# Charge_Controller.net
KiCad netlist of a schematic drawn in EAGLE
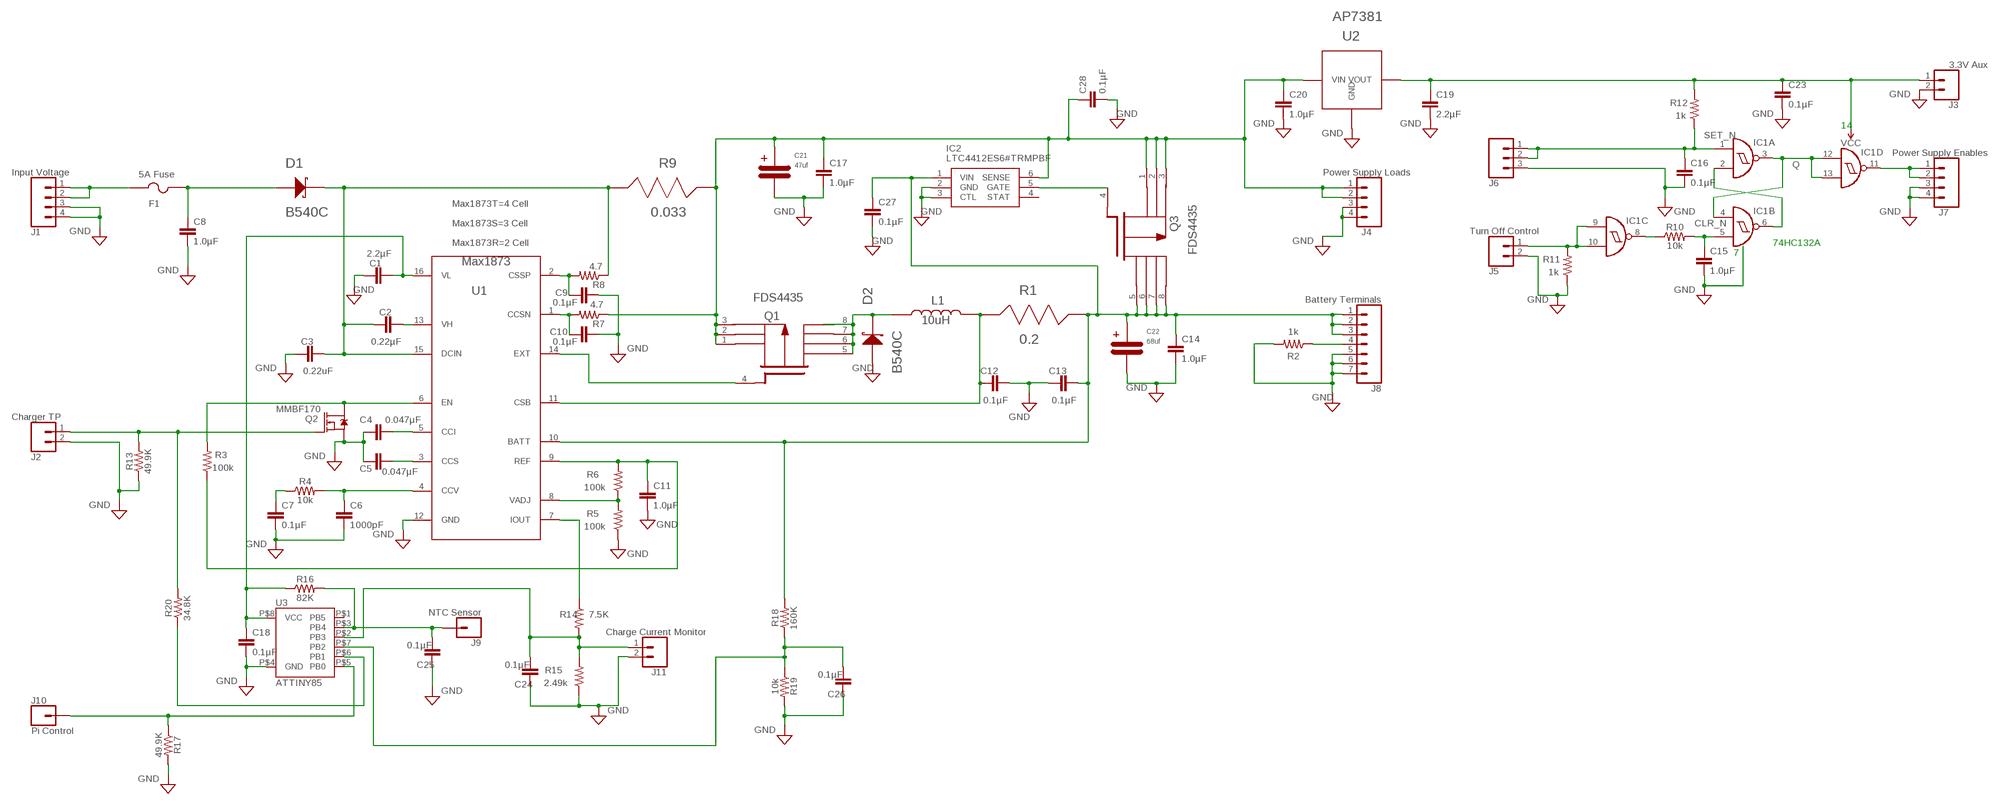
[diagram p0: schematic, sheet 1]

(export (version "E")
  (design (tool "Eeschema 10.0.6"))
  (components
    (comp (ref "C1")
      (value "2.2µF")
      (footprint "eagle-import:0805")
      (libsource (lib "eagle-import") (part "0.33UF/330NF-0805-50V-10%"))
    )
    (comp (ref "C2")
      (value "0.22µF")
      (footprint "eagle-import:0805")
      (libsource (lib "eagle-import") (part "0.33UF/330NF-0805-50V-10%"))
    )
    (comp (ref "C3")
      (value "0.22uF")
      (footprint "eagle-import:0805")
      (libsource (lib "eagle-import") (part "0.33UF/330NF-0805-50V-10%"))
    )
    (comp (ref "C4")
      (value "0.047µF")
      (footprint "eagle-import:0805")
      (libsource (lib "eagle-import") (part "0.33UF/330NF-0805-50V-10%"))
    )
    (comp (ref "C5")
      (value "0.047µF")
      (footprint "eagle-import:0805")
      (libsource (lib "eagle-import") (part "0.33UF/330NF-0805-50V-10%"))
    )
    (comp (ref "C6")
      (value "1000pF")
      (footprint "eagle-import:0805")
      (libsource (lib "eagle-import") (part "0.33UF/330NF-0805-50V-10%"))
    )
    (comp (ref "C7")
      (value "0.1µF")
      (footprint "eagle-import:0805")
      (libsource (lib "eagle-import") (part "0.33UF/330NF-0805-50V-10%"))
    )
    (comp (ref "C8")
      (value "1.0µF")
      (footprint "eagle-import:0805")
      (libsource (lib "eagle-import") (part "0.33UF/330NF-0805-50V-10%"))
    )
    (comp (ref "C9")
      (value "0.1µF")
      (footprint "eagle-import:0805")
      (libsource (lib "eagle-import") (part "0.33UF/330NF-0805-50V-10%"))
    )
    (comp (ref "C10")
      (value "0.1µF")
      (footprint "eagle-import:0805")
      (libsource (lib "eagle-import") (part "0.33UF/330NF-0805-50V-10%"))
    )
    (comp (ref "C11")
      (value "1.0µF")
      (footprint "eagle-import:0805")
      (libsource (lib "eagle-import") (part "0.33UF/330NF-0805-50V-10%"))
    )
    (comp (ref "C12")
      (value "0.1µF")
      (footprint "eagle-import:0805")
      (libsource (lib "eagle-import") (part "0.33UF/330NF-0805-50V-10%"))
    )
    (comp (ref "C13")
      (value "0.1µF")
      (footprint "eagle-import:0805")
      (libsource (lib "eagle-import") (part "0.33UF/330NF-0805-50V-10%"))
    )
    (comp (ref "C14")
      (value "1.0µF")
      (footprint "eagle-import:0805")
      (libsource (lib "eagle-import") (part "0.33UF/330NF-0805-50V-10%"))
    )
    (comp (ref "C15")
      (value "1.0µF")
      (footprint "eagle-import:0805")
      (libsource (lib "eagle-import") (part "0.33UF/330NF-0805-50V-10%"))
    )
    (comp (ref "C16")
      (value "0.1µF")
      (footprint "eagle-import:0805")
      (libsource (lib "eagle-import") (part "0.33UF/330NF-0805-50V-10%"))
    )
    (comp (ref "C17")
      (value "1.0µF")
      (footprint "eagle-import:0805")
      (libsource (lib "eagle-import") (part "0.33UF/330NF-0805-50V-10%"))
    )
    (comp (ref "C18")
      (value "0.1µF")
      (footprint "eagle-import:0805")
      (libsource (lib "eagle-import") (part "0.33UF/330NF-0805-50V-10%"))
    )
    (comp (ref "C19")
      (value "2.2µF")
      (footprint "eagle-import:0805")
      (libsource (lib "eagle-import") (part "0.33UF/330NF-0805-50V-10%"))
    )
    (comp (ref "C20")
      (value "1.0µF")
      (footprint "eagle-import:0805")
      (libsource (lib "eagle-import") (part "0.33UF/330NF-0805-50V-10%"))
    )
    (comp (ref "C21")
      (value "47uf")
      (footprint "eagle-import:2917")
      (libsource (lib "eagle-import") (part "2917"))
    )
    (comp (ref "C22")
      (value "68uf")
      (footprint "eagle-import:2917")
      (libsource (lib "eagle-import") (part "2917"))
    )
    (comp (ref "C23")
      (value "0.1µF")
      (footprint "eagle-import:0805")
      (libsource (lib "eagle-import") (part "0.33UF/330NF-0805-50V-10%"))
    )
    (comp (ref "C24")
      (value "0.1µF")
      (footprint "eagle-import:0805")
      (libsource (lib "eagle-import") (part "0.33UF/330NF-0805-50V-10%"))
    )
    (comp (ref "C25")
      (value "0.1µF")
      (footprint "eagle-import:0805")
      (libsource (lib "eagle-import") (part "0.33UF/330NF-0805-50V-10%"))
    )
    (comp (ref "C26")
      (value "0.1µF")
      (footprint "eagle-import:0805")
      (libsource (lib "eagle-import") (part "0.33UF/330NF-0805-50V-10%"))
    )
    (comp (ref "C27")
      (value "0.1µF")
      (footprint "eagle-import:0805")
      (libsource (lib "eagle-import") (part "0.33UF/330NF-0805-50V-10%"))
    )
    (comp (ref "C28")
      (value "0.1µF")
      (footprint "eagle-import:0805")
      (libsource (lib "eagle-import") (part "0.33UF/330NF-0805-50V-10%"))
    )
    (comp (ref "D1")
      (value "B540C")
      (footprint "eagle-import:B540C")
      (libsource (lib "eagle-import") (part "B540C"))
    )
    (comp (ref "D2")
      (value "B540C")
      (footprint "eagle-import:B540C")
      (libsource (lib "eagle-import") (part "B540C"))
    )
    (comp (ref "F1")
      (value "5A Fuse")
      (footprint "eagle-import:FUSE1206")
      (libsource (lib "eagle-import") (part "FUSE1206"))
    )
    (comp (ref "IC1")
      (value "74132D")
      (footprint "eagle-import:SO14")
      (libsource (lib "eagle-import") (part "74132D"))
    )
    (comp (ref "IC2")
      (value "LTC4412ES6#TRMPBF")
      (footprint "eagle-import:SOT95P280X100-6N")
      (fields (field (name "MOUSER_PART_NUMBER") "584-LTC4412ES6TRMPBF"))
      (libsource (lib "eagle-import") (part "LTC4412ES6#TRMPBF"))
    )
    (comp (ref "J1")
      (value "Input Voltage")
      (footprint "eagle-import:1X04")
      (libsource (lib "eagle-import") (part "SparkFun-Connectors_513_CONN_04"))
    )
    (comp (ref "J2")
      (value "Charger TP")
      (footprint "eagle-import:1X02")
      (libsource (lib "eagle-import") (part "CONN_02"))
    )
    (comp (ref "J3")
      (value "3.3V Aux")
      (footprint "eagle-import:1X02")
      (libsource (lib "eagle-import") (part "CONN_02"))
    )
    (comp (ref "J4")
      (value "Power Supply Loads")
      (footprint "eagle-import:1X04")
      (libsource (lib "eagle-import") (part "CONN_04"))
    )
    (comp (ref "J5")
      (value "Turn Off Control")
      (footprint "eagle-import:1X02")
      (libsource (lib "eagle-import") (part "CONN_02"))
    )
    (comp (ref "J6")
      (value "Turn On")
      (footprint "eagle-import:1X03")
      (libsource (lib "eagle-import") (part "CONN_03"))
    )
    (comp (ref "J7")
      (value "Power Supply Enables")
      (footprint "eagle-import:1X04")
      (libsource (lib "eagle-import") (part "CONN_04"))
    )
    (comp (ref "J8")
      (value "Battery Terminals")
      (footprint "eagle-import:1X07")
      (libsource (lib "eagle-import") (part "CONN_07"))
    )
    (comp (ref "J9")
      (value "NTC Sensor")
      (footprint "eagle-import:1X01")
      (libsource (lib "eagle-import") (part "CONN_01"))
    )
    (comp (ref "J10")
      (value "Pi Control")
      (footprint "eagle-import:1X01")
      (libsource (lib "eagle-import") (part "CONN_01"))
    )
    (comp (ref "J11")
      (value "Charge Current Monitor")
      (footprint "eagle-import:1X02")
      (libsource (lib "eagle-import") (part "CONN_02"))
    )
    (comp (ref "L1")
      (value "10uH")
      (footprint "eagle-import:NRS8030")
      (libsource (lib "eagle-import") (part "NRS8030"))
    )
    (comp (ref "Q1")
      (value "FDS4435")
      (footprint "eagle-import:FDS4435")
      (libsource (lib "eagle-import") (part "FDS4435"))
    )
    (comp (ref "Q2")
      (value "MMBF170")
      (footprint "eagle-import:MMBF170")
      (libsource (lib "eagle-import") (part "MMBF170"))
    )
    (comp (ref "Q3")
      (value "FDS4435")
      (footprint "eagle-import:FDS4435")
      (libsource (lib "eagle-import") (part "FDS4435"))
    )
    (comp (ref "R1")
      (value "0.2")
      (footprint "eagle-import:2512")
      (libsource (lib "eagle-import") (part "2512"))
    )
    (comp (ref "R2")
      (value "1k")
      (footprint "eagle-import:0603")
      (libsource (lib "eagle-import") (part "1KOHM-0603-1/10W-1%"))
    )
    (comp (ref "R3")
      (value "100k")
      (footprint "eagle-import:0603")
      (libsource (lib "eagle-import") (part "100KOHM-0603-1/10W-1%"))
    )
    (comp (ref "R4")
      (value "10k")
      (footprint "eagle-import:0603")
      (libsource (lib "eagle-import") (part "10KOHM-0603-1/10W-1%"))
    )
    (comp (ref "R5")
      (value "100k")
      (footprint "eagle-import:0603")
      (libsource (lib "eagle-import") (part "100KOHM-0603-1/10W-1%"))
    )
    (comp (ref "R6")
      (value "100k")
      (footprint "eagle-import:0603")
      (libsource (lib "eagle-import") (part "100KOHM-0603-1/10W-1%"))
    )
    (comp (ref "R7")
      (value "4.7")
      (footprint "eagle-import:0603_4P7")
      (libsource (lib "eagle-import") (part "0603_4P7"))
    )
    (comp (ref "R8")
      (value "4.7")
      (footprint "eagle-import:0603_4P7")
      (libsource (lib "eagle-import") (part "0603_4P7"))
    )
    (comp (ref "R9")
      (value "0.033")
      (footprint "eagle-import:2512")
      (libsource (lib "eagle-import") (part "2512"))
    )
    (comp (ref "R10")
      (value "10k")
      (footprint "eagle-import:0603")
      (libsource (lib "eagle-import") (part "10KOHM-0603-1/10W-1%"))
    )
    (comp (ref "R11")
      (value "1k")
      (footprint "eagle-import:0603")
      (libsource (lib "eagle-import") (part "1KOHM-0603-1/10W-1%"))
    )
    (comp (ref "R12")
      (value "1k")
      (footprint "eagle-import:0603")
      (libsource (lib "eagle-import") (part "1KOHM-0603-1/10W-1%"))
    )
    (comp (ref "R13")
      (value "49.9K")
      (footprint "eagle-import:0603_RESISTOR")
      (libsource (lib "eagle-import") (part "0603_RESISTOR"))
    )
    (comp (ref "R14")
      (value "7.5K")
      (footprint "eagle-import:0603_RESISTOR")
      (libsource (lib "eagle-import") (part "0603_RESISTOR"))
    )
    (comp (ref "R15")
      (value "2.49k")
      (footprint "eagle-import:0603")
      (libsource (lib "eagle-import") (part "2.49KOHM-0603-1/10W-1%"))
    )
    (comp (ref "R16")
      (value "82K")
      (footprint "eagle-import:0603_RESISTOR")
      (libsource (lib "eagle-import") (part "0603_RESISTOR"))
    )
    (comp (ref "R17")
      (value "49.9K")
      (footprint "eagle-import:0603")
      (libsource (lib "eagle-import") (part "47KOHM-0603-1/10W-1%"))
    )
    (comp (ref "R18")
      (value "160K")
      (footprint "eagle-import:0603_RESISTOR")
      (libsource (lib "eagle-import") (part "0603_RESISTOR"))
    )
    (comp (ref "R19")
      (value "10k")
      (footprint "eagle-import:0603")
      (libsource (lib "eagle-import") (part "SparkFun-Resistors_532_10KOHM-0603-1/10W-1%"))
    )
    (comp (ref "R20")
      (value "34.8K")
      (footprint "eagle-import:0603_RESISTOR")
      (libsource (lib "eagle-import") (part "0603_RESISTOR"))
    )
    (comp (ref "U1")
      (value "Max1873")
      (footprint "eagle-import:MAX1873")
      (libsource (lib "eagle-import") (part "MAX1873"))
    )
    (comp (ref "U2")
      (value "AP7381")
      (footprint "eagle-import:AP7381")
      (libsource (lib "eagle-import") (part "AP7381"))
    )
    (comp (ref "U3")
      (value "ATTINY85")
      (footprint "eagle-import:ATTINY85")
      (libsource (lib "eagle-import") (part "ATTINY85"))
    )
  )
  (nets
    (net (code "1") (name "/CLR_N") (class "Default")
      (node (ref "C15") (pin "1") (pinfunction "1_1") (pintype "passive"))
      (node (ref "IC1") (pin "5") (pinfunction "I1_5") (pintype "input"))
      (node (ref "R10") (pin "2") (pinfunction "2_2") (pintype "passive"))
    )
    (net (code "2") (name "/Q") (class "Default")
      (node (ref "IC1") (pin "12") (pinfunction "I0_12") (pintype "input"))
      (node (ref "IC1") (pin "13") (pinfunction "I1_13") (pintype "input"))
      (node (ref "IC1") (pin "3") (pinfunction "O_3") (pintype "output"))
      (node (ref "IC1") (pin "4") (pinfunction "I0_4") (pintype "input"))
    )
    (net (code "3") (name "/SET_N") (class "Default")
      (node (ref "C16") (pin "1") (pinfunction "1_1") (pintype "passive"))
      (node (ref "IC1") (pin "1") (pinfunction "I0_1") (pintype "input"))
      (node (ref "J6") (pin "1") (pinfunction "1_1") (pintype "passive"))
      (node (ref "J6") (pin "2") (pinfunction "2_2") (pintype "passive"))
      (node (ref "R12") (pin "1") (pinfunction "1_1") (pintype "passive"))
    )
    (net (code "4") (name "GND") (class "Default")
      (node (ref "C1") (pin "1") (pinfunction "1_1") (pintype "passive"))
      (node (ref "C10") (pin "2") (pinfunction "2_2") (pintype "passive"))
      (node (ref "C11") (pin "2") (pinfunction "2_2") (pintype "passive"))
      (node (ref "C12") (pin "2") (pinfunction "2_2") (pintype "passive"))
      (node (ref "C13") (pin "1") (pinfunction "1_1") (pintype "passive"))
      (node (ref "C14") (pin "2") (pinfunction "2_2") (pintype "passive"))
      (node (ref "C15") (pin "2") (pinfunction "2_2") (pintype "passive"))
      (node (ref "C16") (pin "2") (pinfunction "2_2") (pintype "passive"))
      (node (ref "C17") (pin "2") (pinfunction "2_2") (pintype "passive"))
      (node (ref "C18") (pin "2") (pinfunction "2_2") (pintype "passive"))
      (node (ref "C19") (pin "2") (pinfunction "2_2") (pintype "passive"))
      (node (ref "C20") (pin "2") (pinfunction "2_2") (pintype "passive"))
      (node (ref "C21") (pin "NEG") (pinfunction "NEG_NEG") (pintype "bidirectional"))
      (node (ref "C22") (pin "NEG") (pinfunction "NEG_NEG") (pintype "bidirectional"))
      (node (ref "C23") (pin "2") (pinfunction "2_2") (pintype "passive"))
      (node (ref "C24") (pin "1") (pinfunction "1_1") (pintype "passive"))
      (node (ref "C25") (pin "1") (pinfunction "1_1") (pintype "passive"))
      (node (ref "C26") (pin "1") (pinfunction "1_1") (pintype "passive"))
      (node (ref "C27") (pin "2") (pinfunction "2_2") (pintype "passive"))
      (node (ref "C28") (pin "2") (pinfunction "2_2") (pintype "passive"))
      (node (ref "C3") (pin "1") (pinfunction "1_1") (pintype "passive"))
      (node (ref "C4") (pin "1") (pinfunction "1_1") (pintype "passive"))
      (node (ref "C5") (pin "1") (pinfunction "1_1") (pintype "passive"))
      (node (ref "C6") (pin "2") (pinfunction "2_2") (pintype "passive"))
      (node (ref "C7") (pin "2") (pinfunction "2_2") (pintype "passive"))
      (node (ref "C8") (pin "2") (pinfunction "2_2") (pintype "passive"))
      (node (ref "C9") (pin "2") (pinfunction "2_2") (pintype "passive"))
      (node (ref "D2") (pin "P$1") (pinfunction "P$1_P$1") (pintype "bidirectional"))
      (node (ref "IC2") (pin "2") (pinfunction "GND_2") (pintype "bidirectional"))
      (node (ref "IC2") (pin "3") (pinfunction "CTL_3") (pintype "bidirectional"))
      (node (ref "J1") (pin "3") (pinfunction "3_3") (pintype "passive"))
      (node (ref "J1") (pin "4") (pinfunction "4_4") (pintype "passive"))
      (node (ref "J11") (pin "2") (pinfunction "2_2") (pintype "passive"))
      (node (ref "J2") (pin "2") (pinfunction "2_2") (pintype "passive"))
      (node (ref "J3") (pin "2") (pinfunction "2_2") (pintype "passive"))
      (node (ref "J4") (pin "3") (pinfunction "3_3") (pintype "passive"))
      (node (ref "J4") (pin "4") (pinfunction "4_4") (pintype "passive"))
      (node (ref "J5") (pin "2") (pinfunction "2_2") (pintype "passive"))
      (node (ref "J6") (pin "3") (pinfunction "3_3") (pintype "passive"))
      (node (ref "J7") (pin "3") (pinfunction "3_3") (pintype "passive"))
      (node (ref "J7") (pin "4") (pinfunction "4_4") (pintype "passive"))
      (node (ref "J8") (pin "5") (pinfunction "5_5") (pintype "passive"))
      (node (ref "J8") (pin "6") (pinfunction "6_6") (pintype "passive"))
      (node (ref "J8") (pin "7") (pinfunction "7_7") (pintype "passive"))
      (node (ref "Q2") (pin "2") (pinfunction "S_2") (pintype "bidirectional"))
      (node (ref "R11") (pin "1") (pinfunction "1_1") (pintype "passive"))
      (node (ref "R13") (pin "1") (pinfunction "1_1") (pintype "passive"))
      (node (ref "R15") (pin "1") (pinfunction "1_1") (pintype "passive"))
      (node (ref "R17") (pin "2") (pinfunction "2_2") (pintype "passive"))
      (node (ref "R19") (pin "2") (pinfunction "2_2") (pintype "passive"))
      (node (ref "R2") (pin "2") (pinfunction "2_2") (pintype "passive"))
      (node (ref "R5") (pin "1") (pinfunction "1_1") (pintype "passive"))
      (node (ref "U1") (pin "12") (pinfunction "GND_12") (pintype "power_in"))
      (node (ref "U2") (pin "P$3") (pinfunction "GND_P$3") (pintype "bidirectional"))
      (node (ref "U2") (pin "P$4") (pinfunction "GND_P$4") (pintype "bidirectional"))
      (node (ref "U3") (pin "P$4") (pinfunction "GND_P$4") (pintype "bidirectional"))
    )
    (net (code "5") (name "Net-(C7-Pad1)") (class "Default")
      (node (ref "C7") (pin "1") (pinfunction "1_1") (pintype "passive"))
      (node (ref "R4") (pin "1") (pinfunction "1_1") (pintype "passive"))
    )
    (net (code "6") (name "Net-(C8-Pad1)") (class "Default")
      (node (ref "C8") (pin "1") (pinfunction "1_1") (pintype "passive"))
      (node (ref "D1") (pin "P$1") (pinfunction "P$1_P$1") (pintype "bidirectional"))
      (node (ref "F1") (pin "P$2") (pinfunction "P$2_P$2") (pintype "bidirectional"))
    )
    (net (code "7") (name "Net-(F1-PadP$1)") (class "Default")
      (node (ref "F1") (pin "P$1") (pinfunction "P$1_P$1") (pintype "bidirectional"))
      (node (ref "J1") (pin "1") (pinfunction "1_1") (pintype "passive"))
      (node (ref "J1") (pin "2") (pinfunction "2_2") (pintype "passive"))
    )
    (net (code "8") (name "Net-(IC1A-I1)") (class "Default")
      (node (ref "IC1") (pin "2") (pinfunction "I1_2") (pintype "input"))
      (node (ref "IC1") (pin "6") (pinfunction "O_6") (pintype "output"))
    )
    (net (code "9") (name "Net-(IC1C-I0)") (class "Default")
      (node (ref "IC1") (pin "10") (pinfunction "I1_10") (pintype "input"))
      (node (ref "IC1") (pin "9") (pinfunction "I0_9") (pintype "input"))
      (node (ref "J5") (pin "1") (pinfunction "1_1") (pintype "passive"))
      (node (ref "R11") (pin "2") (pinfunction "2_2") (pintype "passive"))
    )
    (net (code "10") (name "Net-(IC1C-O)") (class "Default")
      (node (ref "IC1") (pin "8") (pinfunction "O_8") (pintype "output"))
      (node (ref "R10") (pin "1") (pinfunction "1_1") (pintype "passive"))
    )
    (net (code "11") (name "Net-(IC1D-O)") (class "Default")
      (node (ref "IC1") (pin "11") (pinfunction "O_11") (pintype "output"))
      (node (ref "J7") (pin "1") (pinfunction "1_1") (pintype "passive"))
      (node (ref "J7") (pin "2") (pinfunction "2_2") (pintype "passive"))
    )
    (net (code "12") (name "Net-(IC2-GATE)") (class "Default")
      (node (ref "IC2") (pin "5") (pinfunction "GATE_5") (pintype "bidirectional"))
      (node (ref "Q3") (pin "4") (pinfunction "G4_4") (pintype "bidirectional"))
    )
    (net (code "13") (name "Net-(IC2-SENSE)") (class "Default")
      (node (ref "C17") (pin "1") (pinfunction "1_1") (pintype "passive"))
      (node (ref "C20") (pin "1") (pinfunction "1_1") (pintype "passive"))
      (node (ref "C21") (pin "POS") (pinfunction "POS_POS") (pintype "bidirectional"))
      (node (ref "C28") (pin "1") (pinfunction "1_1") (pintype "passive"))
      (node (ref "IC2") (pin "6") (pinfunction "SENSE_6") (pintype "bidirectional"))
      (node (ref "J4") (pin "1") (pinfunction "1_1") (pintype "passive"))
      (node (ref "J4") (pin "2") (pinfunction "2_2") (pintype "passive"))
      (node (ref "Q1") (pin "1") (pinfunction "S1_1") (pintype "bidirectional"))
      (node (ref "Q1") (pin "2") (pinfunction "S2_2") (pintype "bidirectional"))
      (node (ref "Q1") (pin "3") (pinfunction "S3_3") (pintype "bidirectional"))
      (node (ref "Q3") (pin "1") (pinfunction "S1_1") (pintype "bidirectional"))
      (node (ref "Q3") (pin "2") (pinfunction "S2_2") (pintype "bidirectional"))
      (node (ref "Q3") (pin "3") (pinfunction "S3_3") (pintype "bidirectional"))
      (node (ref "R7") (pin "1") (pinfunction "1_1") (pintype "passive"))
      (node (ref "R9") (pin "P$1") (pinfunction "P$1_P$1") (pintype "bidirectional"))
      (node (ref "U2") (pin "P$2") (pinfunction "VIN_P$2") (pintype "bidirectional"))
    )
    (net (code "14") (name "Net-(IC2-VIN)") (class "Default")
      (node (ref "C13") (pin "2") (pinfunction "2_2") (pintype "passive"))
      (node (ref "C14") (pin "1") (pinfunction "1_1") (pintype "passive"))
      (node (ref "C22") (pin "POS") (pinfunction "POS_POS") (pintype "bidirectional"))
      (node (ref "C27") (pin "1") (pinfunction "1_1") (pintype "passive"))
      (node (ref "IC2") (pin "1") (pinfunction "VIN_1") (pintype "bidirectional"))
      (node (ref "J8") (pin "1") (pinfunction "1_1") (pintype "passive"))
      (node (ref "J8") (pin "2") (pinfunction "2_2") (pintype "passive"))
      (node (ref "J8") (pin "3") (pinfunction "3_3") (pintype "passive"))
      (node (ref "Q3") (pin "5") (pinfunction "D5_5") (pintype "bidirectional"))
      (node (ref "Q3") (pin "6") (pinfunction "D6_6") (pintype "bidirectional"))
      (node (ref "Q3") (pin "7") (pinfunction "D7_7") (pintype "bidirectional"))
      (node (ref "Q3") (pin "8") (pinfunction "D8_8") (pintype "bidirectional"))
      (node (ref "R1") (pin "P$2") (pinfunction "P$2_P$2") (pintype "bidirectional"))
      (node (ref "R18") (pin "2") (pinfunction "2_2") (pintype "passive"))
      (node (ref "U1") (pin "10") (pinfunction "BATT_10") (pintype "bidirectional"))
    )
    (net (code "15") (name "Net-(J8-Pad4)") (class "Default")
      (node (ref "J8") (pin "4") (pinfunction "4_4") (pintype "passive"))
      (node (ref "R2") (pin "1") (pinfunction "1_1") (pintype "passive"))
    )
    (net (code "16") (name "Net-(Q1-D5)") (class "Default")
      (node (ref "D2") (pin "P$2") (pinfunction "P$2_P$2") (pintype "bidirectional"))
      (node (ref "L1") (pin "P$1") (pinfunction "P$1_P$1") (pintype "bidirectional"))
      (node (ref "Q1") (pin "5") (pinfunction "D5_5") (pintype "bidirectional"))
      (node (ref "Q1") (pin "6") (pinfunction "D6_6") (pintype "bidirectional"))
      (node (ref "Q1") (pin "7") (pinfunction "D7_7") (pintype "bidirectional"))
      (node (ref "Q1") (pin "8") (pinfunction "D8_8") (pintype "bidirectional"))
    )
    (net (code "17") (name "Net-(Q1-G4)") (class "Default")
      (node (ref "Q1") (pin "4") (pinfunction "G4_4") (pintype "bidirectional"))
      (node (ref "U1") (pin "14") (pinfunction "EXT_14") (pintype "bidirectional"))
    )
    (net (code "18") (name "Net-(Q2-D)") (class "Default")
      (node (ref "Q2") (pin "3") (pinfunction "D_3") (pintype "bidirectional"))
      (node (ref "R3") (pin "2") (pinfunction "2_2") (pintype "passive"))
      (node (ref "U1") (pin "6") (pinfunction "EN_6") (pintype "bidirectional"))
    )
    (net (code "19") (name "Net-(Q2-G)") (class "Default")
      (node (ref "J2") (pin "1") (pinfunction "1_1") (pintype "passive"))
      (node (ref "Q2") (pin "1") (pinfunction "G_1") (pintype "bidirectional"))
      (node (ref "R13") (pin "2") (pinfunction "2_2") (pintype "passive"))
      (node (ref "R20") (pin "2") (pinfunction "2_2") (pintype "passive"))
    )
    (net (code "20") (name "Net-(U1-CCI)") (class "Default")
      (node (ref "C4") (pin "2") (pinfunction "2_2") (pintype "passive"))
      (node (ref "U1") (pin "5") (pinfunction "CCI_5") (pintype "bidirectional"))
    )
    (net (code "21") (name "Net-(U1-CCS)") (class "Default")
      (node (ref "C5") (pin "2") (pinfunction "2_2") (pintype "passive"))
      (node (ref "U1") (pin "3") (pinfunction "CCS_3") (pintype "bidirectional"))
    )
    (net (code "22") (name "Net-(U1-CCSN)") (class "Default")
      (node (ref "C10") (pin "1") (pinfunction "1_1") (pintype "passive"))
      (node (ref "R7") (pin "2") (pinfunction "2_2") (pintype "passive"))
      (node (ref "U1") (pin "1") (pinfunction "CCSN_1") (pintype "bidirectional"))
    )
    (net (code "23") (name "Net-(U1-CCV)") (class "Default")
      (node (ref "C6") (pin "1") (pinfunction "1_1") (pintype "passive"))
      (node (ref "R4") (pin "2") (pinfunction "2_2") (pintype "passive"))
      (node (ref "U1") (pin "4") (pinfunction "CCV_4") (pintype "bidirectional"))
    )
    (net (code "24") (name "Net-(U1-CSB)") (class "Default")
      (node (ref "C12") (pin "1") (pinfunction "1_1") (pintype "passive"))
      (node (ref "L1") (pin "P$2") (pinfunction "P$2_P$2") (pintype "bidirectional"))
      (node (ref "R1") (pin "P$1") (pinfunction "P$1_P$1") (pintype "bidirectional"))
      (node (ref "U1") (pin "11") (pinfunction "CSB_11") (pintype "bidirectional"))
    )
    (net (code "25") (name "Net-(U1-CSSP)") (class "Default")
      (node (ref "C9") (pin "1") (pinfunction "1_1") (pintype "passive"))
      (node (ref "R8") (pin "2") (pinfunction "2_2") (pintype "passive"))
      (node (ref "U1") (pin "2") (pinfunction "CSSP_2") (pintype "bidirectional"))
    )
    (net (code "26") (name "Net-(U1-DCIN)") (class "Default")
      (node (ref "C2") (pin "1") (pinfunction "1_1") (pintype "passive"))
      (node (ref "C3") (pin "2") (pinfunction "2_2") (pintype "passive"))
      (node (ref "D1") (pin "P$2") (pinfunction "P$2_P$2") (pintype "bidirectional"))
      (node (ref "R8") (pin "1") (pinfunction "1_1") (pintype "passive"))
      (node (ref "R9") (pin "P$2") (pinfunction "P$2_P$2") (pintype "bidirectional"))
      (node (ref "U1") (pin "15") (pinfunction "DCIN_15") (pintype "bidirectional"))
    )
    (net (code "27") (name "Net-(U1-IOUT)") (class "Default")
      (node (ref "R14") (pin "1") (pinfunction "1_1") (pintype "passive"))
      (node (ref "U1") (pin "7") (pinfunction "IOUT_7") (pintype "bidirectional"))
    )
    (net (code "28") (name "Net-(U1-REF)") (class "Default")
      (node (ref "C11") (pin "1") (pinfunction "1_1") (pintype "passive"))
      (node (ref "R3") (pin "1") (pinfunction "1_1") (pintype "passive"))
      (node (ref "R6") (pin "2") (pinfunction "2_2") (pintype "passive"))
      (node (ref "U1") (pin "9") (pinfunction "REF_9") (pintype "bidirectional"))
    )
    (net (code "29") (name "Net-(U1-VADJ)") (class "Default")
      (node (ref "R5") (pin "2") (pinfunction "2_2") (pintype "passive"))
      (node (ref "R6") (pin "1") (pinfunction "1_1") (pintype "passive"))
      (node (ref "U1") (pin "8") (pinfunction "VADJ_8") (pintype "bidirectional"))
    )
    (net (code "30") (name "Net-(U1-VH)") (class "Default")
      (node (ref "C2") (pin "2") (pinfunction "2_2") (pintype "passive"))
      (node (ref "U1") (pin "13") (pinfunction "VH_13") (pintype "bidirectional"))
    )
    (net (code "31") (name "Net-(U1-VL)") (class "Default")
      (node (ref "C1") (pin "2") (pinfunction "2_2") (pintype "passive"))
      (node (ref "C18") (pin "1") (pinfunction "1_1") (pintype "passive"))
      (node (ref "R16") (pin "1") (pinfunction "1_1") (pintype "passive"))
      (node (ref "U1") (pin "16") (pinfunction "VL_16") (pintype "bidirectional"))
      (node (ref "U3") (pin "P$8") (pinfunction "VCC_P$8") (pintype "bidirectional"))
    )
    (net (code "32") (name "Net-(U3-PB0)") (class "Default")
      (node (ref "J10") (pin "1") (pinfunction "1_1") (pintype "passive"))
      (node (ref "R17") (pin "1") (pinfunction "1_1") (pintype "passive"))
      (node (ref "U3") (pin "P$5") (pinfunction "PB0_P$5") (pintype "bidirectional"))
    )
    (net (code "33") (name "Net-(U3-PB1)") (class "Default")
      (node (ref "R20") (pin "1") (pinfunction "1_1") (pintype "passive"))
      (node (ref "U3") (pin "P$6") (pinfunction "PB1_P$6") (pintype "bidirectional"))
    )
    (net (code "34") (name "Net-(U3-PB2)") (class "Default")
      (node (ref "C26") (pin "2") (pinfunction "2_2") (pintype "passive"))
      (node (ref "R18") (pin "1") (pinfunction "1_1") (pintype "passive"))
      (node (ref "R19") (pin "1") (pinfunction "1_1") (pintype "passive"))
      (node (ref "U3") (pin "P$7") (pinfunction "PB2_P$7") (pintype "bidirectional"))
    )
    (net (code "35") (name "Net-(U3-PB3)") (class "Default")
      (node (ref "C24") (pin "2") (pinfunction "2_2") (pintype "passive"))
      (node (ref "J11") (pin "1") (pinfunction "1_1") (pintype "passive"))
      (node (ref "R14") (pin "2") (pinfunction "2_2") (pintype "passive"))
      (node (ref "R15") (pin "2") (pinfunction "2_2") (pintype "passive"))
      (node (ref "U3") (pin "P$2") (pinfunction "PB3_P$2") (pintype "bidirectional"))
    )
    (net (code "36") (name "Net-(U3-PB4)") (class "Default")
      (node (ref "C25") (pin "2") (pinfunction "2_2") (pintype "passive"))
      (node (ref "J9") (pin "1") (pinfunction "1_1") (pintype "passive"))
      (node (ref "R16") (pin "2") (pinfunction "2_2") (pintype "passive"))
      (node (ref "U3") (pin "P$3") (pinfunction "PB4_P$3") (pintype "bidirectional"))
    )
    (net (code "37") (name "VCC") (class "Default")
      (node (ref "C19") (pin "1") (pinfunction "1_1") (pintype "passive"))
      (node (ref "C23") (pin "1") (pinfunction "1_1") (pintype "passive"))
      (node (ref "J3") (pin "1") (pinfunction "1_1") (pintype "passive"))
      (node (ref "R12") (pin "2") (pinfunction "2_2") (pintype "passive"))
      (node (ref "U2") (pin "P$1") (pinfunction "VOUT_P$1") (pintype "bidirectional"))
    )
    (net (code "38") (name "unconnected-(IC2-STAT-Pad4)") (class "Default")
      (node (ref "IC2") (pin "4") (pinfunction "STAT_4") (pintype "bidirectional"))
    )
    (net (code "39") (name "unconnected-(U3-PB5-PadP$1)") (class "Default")
      (node (ref "U3") (pin "P$1") (pinfunction "PB5_P$1") (pintype "bidirectional"))
    )
  )
)
